# 328_ch340g.net
KiCad netlist of a schematic drawn in EAGLE
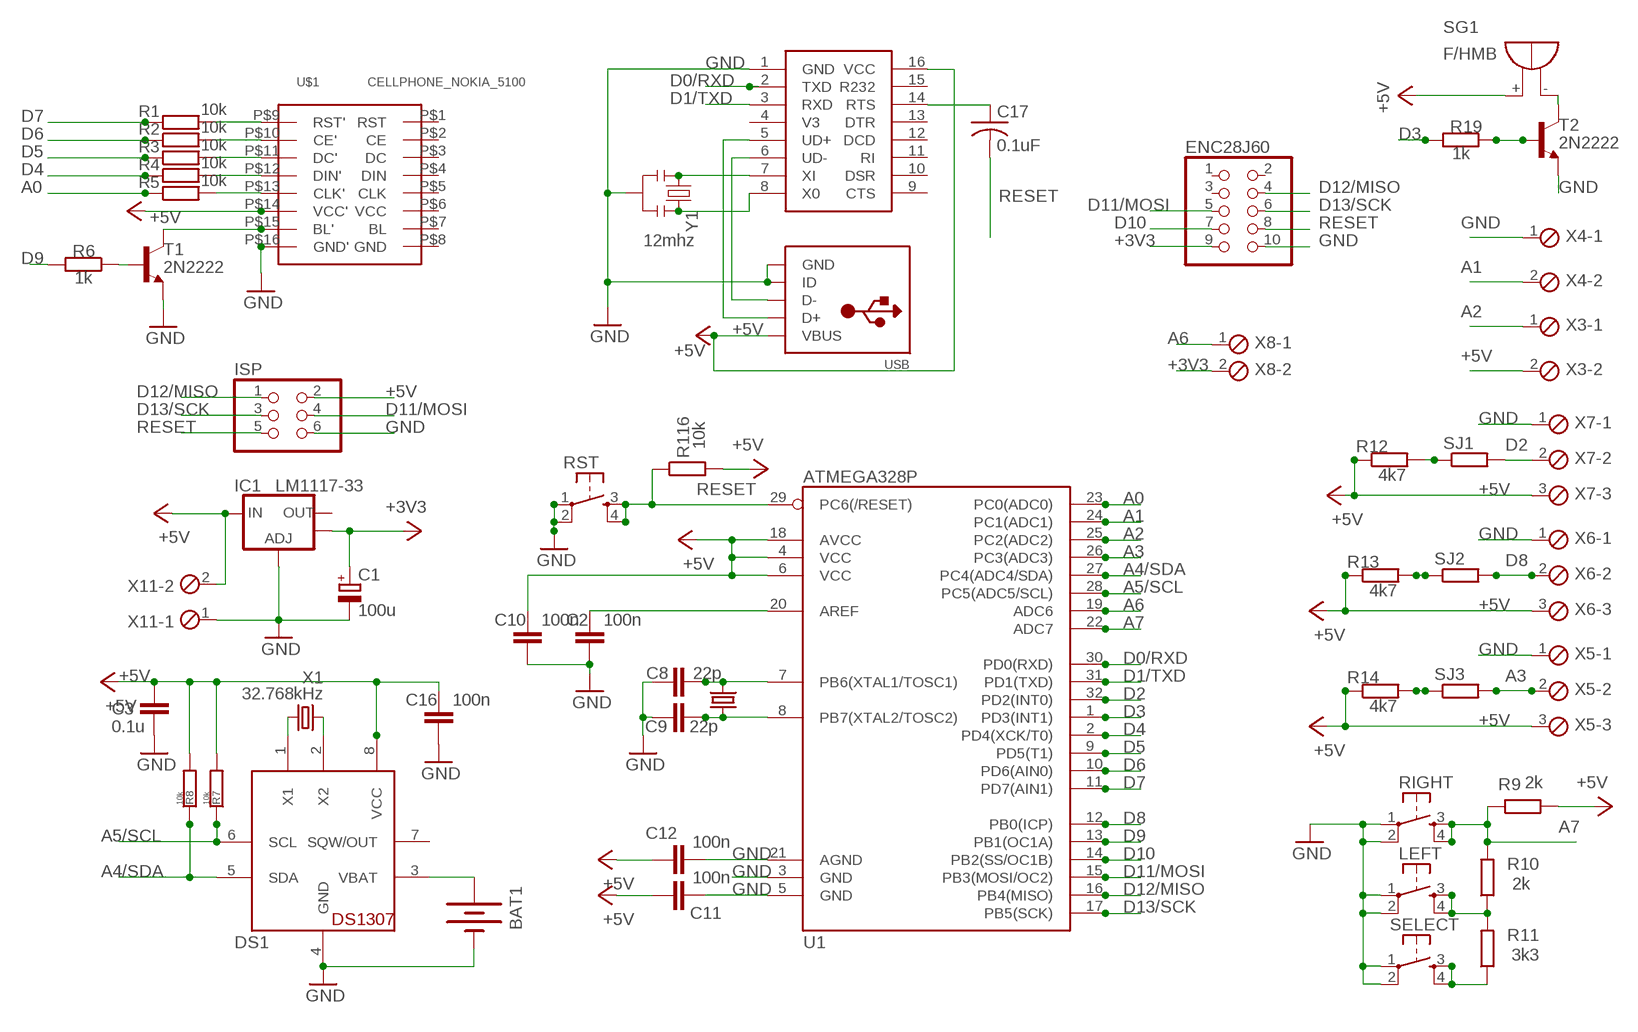
[diagram p0: schematic, sheet 1]

(export (version "E")
  (design (tool "Eeschema 10.0.6"))
  (components
    (comp (ref "BAT1")
      (value "BATTERY20PTH")
      (footprint "eagle-import:BATTCOM_20MM_PTH")
      (libsource (lib "eagle-import") (part "BATTERY20PTH"))
    )
    (comp (ref "C1")
      (value "100u")
      (footprint "eagle-import:E2-5")
      (libsource (lib "eagle-import") (part "CPOL-EUE2-5"))
    )
    (comp (ref "C2")
      (value "100n")
      (footprint "eagle-import:C0805")
      (libsource (lib "eagle-import") (part "resistor_C-EUC0805"))
    )
    (comp (ref "C3")
      (value "0.1u")
      (footprint "eagle-import:C0805")
      (libsource (lib "eagle-import") (part "C-EUC0805"))
    )
    (comp (ref "C8")
      (value "22p")
      (footprint "eagle-import:C0805")
      (libsource (lib "eagle-import") (part "resistor_C-EUC0805"))
    )
    (comp (ref "C9")
      (value "22p")
      (footprint "eagle-import:C0805")
      (libsource (lib "eagle-import") (part "resistor_C-EUC0805"))
    )
    (comp (ref "C10")
      (value "100n")
      (footprint "eagle-import:C0805")
      (libsource (lib "eagle-import") (part "resistor_C-EUC0805"))
    )
    (comp (ref "C11")
      (value "100n")
      (footprint "eagle-import:C0805")
      (libsource (lib "eagle-import") (part "resistor_C-EUC0805"))
    )
    (comp (ref "C12")
      (value "100n")
      (footprint "eagle-import:C0805")
      (libsource (lib "eagle-import") (part "resistor_C-EUC0805"))
    )
    (comp (ref "C16")
      (value "100n")
      (footprint "eagle-import:C0805")
      (libsource (lib "eagle-import") (part "resistor_C-EUC0805"))
    )
    (comp (ref "C17")
      (value "0.1uF")
      (footprint "eagle-import:C0805K")
      (libsource (lib "eagle-import") (part "C-USC0805K"))
    )
    (comp (ref "DS1")
      (value "DS1307")
      (footprint "eagle-import:SO08")
      (libsource (lib "eagle-import") (part "DS1307SOIC"))
    )
    (comp (ref "ENC28J60")
      (value "PINHD-2X5")
      (footprint "eagle-import:2X05")
      (libsource (lib "eagle-import") (part "PINHD-2X5"))
    )
    (comp (ref "IC1")
      (value "LM1117-33")
      (footprint "eagle-import:SOT223")
      (libsource (lib "eagle-import") (part "V_REG_LM1117SOT223"))
    )
    (comp (ref "ISP")
      (value "PINHD-2X3")
      (footprint "eagle-import:2X03")
      (libsource (lib "eagle-import") (part "PINHD-2X3"))
    )
    (comp (ref "LEFT")
      (value "TAC_SWITCHPTH")
      (footprint "eagle-import:TACTILE-PTH")
      (libsource (lib "eagle-import") (part "TAC_SWITCHPTH"))
    )
    (comp (ref "R1")
      (value "10k")
      (footprint "eagle-import:R0805")
      (libsource (lib "eagle-import") (part "R-EU_R0805"))
    )
    (comp (ref "R2")
      (value "10k")
      (footprint "eagle-import:R0805")
      (libsource (lib "eagle-import") (part "R-EU_R0805"))
    )
    (comp (ref "R3")
      (value "10k")
      (footprint "eagle-import:R0805")
      (libsource (lib "eagle-import") (part "R-EU_R0805"))
    )
    (comp (ref "R4")
      (value "10k")
      (footprint "eagle-import:R0805")
      (libsource (lib "eagle-import") (part "R-EU_R0805"))
    )
    (comp (ref "R5")
      (value "10k")
      (footprint "eagle-import:R0805")
      (libsource (lib "eagle-import") (part "R-EU_R0805"))
    )
    (comp (ref "R6")
      (value "1k")
      (footprint "eagle-import:R0805")
      (libsource (lib "eagle-import") (part "R-EU_R0805"))
    )
    (comp (ref "R7")
      (value "10k")
      (footprint "eagle-import:R0805")
      (libsource (lib "eagle-import") (part "R-EU_R0805"))
    )
    (comp (ref "R8")
      (value "10k")
      (footprint "eagle-import:R0805")
      (libsource (lib "eagle-import") (part "R-EU_R0805"))
    )
    (comp (ref "R9")
      (value "2k")
      (footprint "eagle-import:R0805")
      (libsource (lib "eagle-import") (part "R-EU_R0805"))
    )
    (comp (ref "R10")
      (value "2k")
      (footprint "eagle-import:R0805")
      (libsource (lib "eagle-import") (part "R-EU_R0805"))
    )
    (comp (ref "R11")
      (value "3k3")
      (footprint "eagle-import:R0805")
      (libsource (lib "eagle-import") (part "R-EU_R0805"))
    )
    (comp (ref "R12")
      (value "4k7")
      (footprint "eagle-import:R0805")
      (libsource (lib "eagle-import") (part "R-EU_R0805"))
    )
    (comp (ref "R13")
      (value "4k7")
      (footprint "eagle-import:R0805")
      (libsource (lib "eagle-import") (part "R-EU_R0805"))
    )
    (comp (ref "R14")
      (value "4k7")
      (footprint "eagle-import:R0805")
      (libsource (lib "eagle-import") (part "R-EU_R0805"))
    )
    (comp (ref "R19")
      (value "1k")
      (footprint "eagle-import:R0805")
      (libsource (lib "eagle-import") (part "R-EU_R0805"))
    )
    (comp (ref "R116")
      (value "10k")
      (footprint "eagle-import:R0805")
      (libsource (lib "eagle-import") (part "R-EU_R0805"))
    )
    (comp (ref "RIGHT")
      (value "TAC_SWITCHPTH")
      (footprint "eagle-import:TACTILE-PTH")
      (libsource (lib "eagle-import") (part "TAC_SWITCHPTH"))
    )
    (comp (ref "RST")
      (value "TAC_SWITCHPTH")
      (footprint "eagle-import:TACTILE-PTH")
      (libsource (lib "eagle-import") (part "TAC_SWITCHPTH"))
    )
    (comp (ref "SELECT")
      (value "TAC_SWITCHPTH")
      (footprint "eagle-import:TACTILE-PTH")
      (libsource (lib "eagle-import") (part "TAC_SWITCHPTH"))
    )
    (comp (ref "SG1")
      (value "F/HMB")
      (footprint "eagle-import:F_HMB")
      (libsource (lib "eagle-import") (part "F/HMB"))
    )
    (comp (ref "SJ1")
      (value "R-EU_R0402")
      (footprint "eagle-import:R0402")
      (libsource (lib "eagle-import") (part "R-EU_R0402"))
    )
    (comp (ref "SJ2")
      (value "R-EU_R0402")
      (footprint "eagle-import:R0402")
      (libsource (lib "eagle-import") (part "R-EU_R0402"))
    )
    (comp (ref "SJ3")
      (value "R-EU_R0402")
      (footprint "eagle-import:R0402")
      (libsource (lib "eagle-import") (part "R-EU_R0402"))
    )
    (comp (ref "T1")
      (value "2N2222")
      (footprint "eagle-import:TO92-EBC-OVAL")
      (libsource (lib "eagle-import") (part "2N2222"))
    )
    (comp (ref "T2")
      (value "2N2222")
      (footprint "eagle-import:TO92-EBC-OVAL")
      (libsource (lib "eagle-import") (part "2N2222"))
    )
    (comp (ref "U$1")
      (value "CELLPHONE_NOKIA_5100")
      (footprint "eagle-import:CELLPHONE_NOKIA_5100_SPARKFUN")
      (libsource (lib "eagle-import") (part "CELLPHONE_NOKIA_5100"))
    )
    (comp (ref "U$2")
      (value "CH340G")
      (footprint "eagle-import:SO016")
      (libsource (lib "eagle-import") (part "CH340G"))
    )
    (comp (ref "U1")
      (value "ATMEGA328P")
      (footprint "eagle-import:TQFP32-08")
      (libsource (lib "eagle-import") (part "ATMEGA328_SMT"))
    )
    (comp (ref "USB")
      (value "USBMOLEX")
      (footprint "eagle-import:USB-MINIB-THM-MOLEX")
      (libsource (lib "eagle-import") (part "USBMOLEX"))
    )
    (comp (ref "X1")
      (value "32.768kHz")
      (footprint "eagle-import:TC26H")
      (libsource (lib "eagle-import") (part "crystal_CRYSTALTC26H"))
    )
    (comp (ref "X2")
      (value "16MHz")
      (footprint "eagle-import:HC49US")
      (libsource (lib "eagle-import") (part "CRYSTALHC49US"))
    )
    (comp (ref "X3")
      (value "MPT2")
      (footprint "eagle-import:2POL254")
      (libsource (lib "eagle-import") (part "MPT2"))
    )
    (comp (ref "X4")
      (value "MPT2")
      (footprint "eagle-import:2POL254")
      (libsource (lib "eagle-import") (part "MPT2"))
    )
    (comp (ref "X5")
      (value "MPT3")
      (footprint "eagle-import:3POL254")
      (libsource (lib "eagle-import") (part "MPT3"))
    )
    (comp (ref "X6")
      (value "MPT3")
      (footprint "eagle-import:3POL254")
      (libsource (lib "eagle-import") (part "MPT3"))
    )
    (comp (ref "X7")
      (value "MPT3")
      (footprint "eagle-import:3POL254")
      (libsource (lib "eagle-import") (part "MPT3"))
    )
    (comp (ref "X8")
      (value "MPT2")
      (footprint "eagle-import:2POL254")
      (libsource (lib "eagle-import") (part "MPT2"))
    )
    (comp (ref "X11")
      (value "MPT2")
      (footprint "eagle-import:2POL254")
      (fields (field (name "OC_FARNELL") "unknown") (field (name "OC_NEWARK") "unknown"))
      (libsource (lib "eagle-import") (part "MPT2"))
    )
    (comp (ref "Y1")
      (value "12mhz")
      (footprint "eagle-import:RESONATOR-PTH")
      (libsource (lib "eagle-import") (part "RESONATORPTH"))
    )
  )
  (nets
    (net (code "1") (name "+3V3") (class "Default")
      (node (ref "C1") (pin "+") (pinfunction "+_+") (pintype "passive"))
      (node (ref "ENC28J60") (pin "9") (pinfunction "9_9") (pintype "passive"))
      (node (ref "IC1") (pin "4") (pinfunction "OUT_4") (pintype "bidirectional"))
      (node (ref "X8") (pin "2") (pinfunction "1_2") (pintype "passive"))
    )
    (net (code "2") (name "+5V") (class "Default")
      (node (ref "C10") (pin "1") (pinfunction "1_1") (pintype "passive"))
      (node (ref "C11") (pin "2") (pinfunction "2_2") (pintype "passive"))
      (node (ref "C12") (pin "2") (pinfunction "2_2") (pintype "passive"))
      (node (ref "C16") (pin "1") (pinfunction "1_1") (pintype "passive"))
      (node (ref "C3") (pin "1") (pinfunction "1_1") (pintype "passive"))
      (node (ref "DS1") (pin "8") (pinfunction "VCC_8") (pintype "power_in"))
      (node (ref "IC1") (pin "3") (pinfunction "IN_3") (pintype "input"))
      (node (ref "ISP") (pin "2") (pinfunction "2_2") (pintype "passive"))
      (node (ref "R116") (pin "2") (pinfunction "2_2") (pintype "passive"))
      (node (ref "R12") (pin "1") (pinfunction "1_1") (pintype "passive"))
      (node (ref "R13") (pin "1") (pinfunction "1_1") (pintype "passive"))
      (node (ref "R14") (pin "1") (pinfunction "1_1") (pintype "passive"))
      (node (ref "R7") (pin "2") (pinfunction "2_2") (pintype "passive"))
      (node (ref "R8") (pin "2") (pinfunction "2_2") (pintype "passive"))
      (node (ref "R9") (pin "2") (pinfunction "2_2") (pintype "passive"))
      (node (ref "SG1") (pin "+") (pinfunction "+_+") (pintype "passive"))
      (node (ref "U$1") (pin "P$14") (pinfunction "VCC'_P$14") (pintype "bidirectional"))
      (node (ref "U$2") (pin "16") (pinfunction "VCC_16") (pintype "bidirectional"))
      (node (ref "U1") (pin "18") (pinfunction "AVCC_18") (pintype "bidirectional"))
      (node (ref "U1") (pin "4") (pinfunction "VCC_4") (pintype "bidirectional"))
      (node (ref "U1") (pin "6") (pinfunction "VCC_6") (pintype "bidirectional"))
      (node (ref "USB") (pin "VBUS") (pinfunction "VBUS_VBUS") (pintype "power_in"))
      (node (ref "X11") (pin "2") (pinfunction "1_2") (pintype "passive"))
      (node (ref "X3") (pin "2") (pinfunction "1_2") (pintype "passive"))
      (node (ref "X5") (pin "3") (pinfunction "1_3") (pintype "passive"))
      (node (ref "X6") (pin "3") (pinfunction "1_3") (pintype "passive"))
      (node (ref "X7") (pin "3") (pinfunction "1_3") (pintype "passive"))
    )
    (net (code "3") (name "/A0") (class "Default")
      (node (ref "R5") (pin "1") (pinfunction "1_1") (pintype "passive"))
      (node (ref "U1") (pin "23") (pinfunction "PC0(ADC0)_23") (pintype "bidirectional"))
    )
    (net (code "4") (name "/A1") (class "Default")
      (node (ref "U1") (pin "24") (pinfunction "PC1(ADC1)_24") (pintype "bidirectional"))
      (node (ref "X4") (pin "2") (pinfunction "1_2") (pintype "passive"))
    )
    (net (code "5") (name "/A2") (class "Default")
      (node (ref "U1") (pin "25") (pinfunction "PC2(ADC2)_25") (pintype "bidirectional"))
      (node (ref "X3") (pin "1") (pinfunction "1_1") (pintype "passive"))
    )
    (net (code "6") (name "/A3") (class "Default")
      (node (ref "SJ3") (pin "2") (pinfunction "2_2") (pintype "passive"))
      (node (ref "U1") (pin "26") (pinfunction "PC3(ADC3)_26") (pintype "bidirectional"))
      (node (ref "X5") (pin "2") (pinfunction "1_2") (pintype "passive"))
    )
    (net (code "7") (name "/A4{slash}SDA") (class "Default")
      (node (ref "DS1") (pin "5") (pinfunction "SDA_5") (pintype "bidirectional"))
      (node (ref "R8") (pin "1") (pinfunction "1_1") (pintype "passive"))
      (node (ref "U1") (pin "27") (pinfunction "PC4(ADC4/SDA)_27") (pintype "bidirectional"))
    )
    (net (code "8") (name "/A5{slash}SCL") (class "Default")
      (node (ref "DS1") (pin "6") (pinfunction "SCL_6") (pintype "bidirectional"))
      (node (ref "R7") (pin "1") (pinfunction "1_1") (pintype "passive"))
      (node (ref "U1") (pin "28") (pinfunction "PC5(ADC5/SCL)_28") (pintype "bidirectional"))
    )
    (net (code "9") (name "/A6") (class "Default")
      (node (ref "U1") (pin "19") (pinfunction "ADC6_19") (pintype "bidirectional"))
      (node (ref "X8") (pin "1") (pinfunction "1_1") (pintype "passive"))
    )
    (net (code "10") (name "/A7") (class "Default")
      (node (ref "R10") (pin "2") (pinfunction "2_2") (pintype "passive"))
      (node (ref "R9") (pin "1") (pinfunction "1_1") (pintype "passive"))
      (node (ref "RIGHT") (pin "3") (pinfunction "3_3") (pintype "passive"))
      (node (ref "RIGHT") (pin "4") (pinfunction "4_4") (pintype "passive"))
      (node (ref "U1") (pin "22") (pinfunction "ADC7_22") (pintype "bidirectional"))
    )
    (net (code "11") (name "/D0{slash}RXD") (class "Default")
      (node (ref "U$2") (pin "2") (pinfunction "TXD_2") (pintype "bidirectional"))
      (node (ref "U1") (pin "30") (pinfunction "PD0(RXD)_30") (pintype "bidirectional"))
    )
    (net (code "12") (name "/D1{slash}TXD") (class "Default")
      (node (ref "U$2") (pin "3") (pinfunction "RXD_3") (pintype "bidirectional"))
      (node (ref "U1") (pin "31") (pinfunction "PD1(TXD)_31") (pintype "bidirectional"))
    )
    (net (code "13") (name "/D2") (class "Default")
      (node (ref "SJ1") (pin "2") (pinfunction "2_2") (pintype "passive"))
      (node (ref "U1") (pin "32") (pinfunction "PD2(INT0)_32") (pintype "bidirectional"))
      (node (ref "X7") (pin "2") (pinfunction "1_2") (pintype "passive"))
    )
    (net (code "14") (name "/D3") (class "Default")
      (node (ref "R19") (pin "2") (pinfunction "2_2") (pintype "passive"))
      (node (ref "U1") (pin "1") (pinfunction "PD3(INT1)_1") (pintype "bidirectional"))
    )
    (net (code "15") (name "/D4") (class "Default")
      (node (ref "R4") (pin "1") (pinfunction "1_1") (pintype "passive"))
      (node (ref "U1") (pin "2") (pinfunction "PD4(XCK/T0)_2") (pintype "bidirectional"))
    )
    (net (code "16") (name "/D5") (class "Default")
      (node (ref "R3") (pin "1") (pinfunction "1_1") (pintype "passive"))
      (node (ref "U1") (pin "9") (pinfunction "PD5(T1)_9") (pintype "bidirectional"))
    )
    (net (code "17") (name "/D6") (class "Default")
      (node (ref "R2") (pin "1") (pinfunction "1_1") (pintype "passive"))
      (node (ref "U1") (pin "10") (pinfunction "PD6(AIN0)_10") (pintype "bidirectional"))
    )
    (net (code "18") (name "/D7") (class "Default")
      (node (ref "R1") (pin "1") (pinfunction "1_1") (pintype "passive"))
      (node (ref "U1") (pin "11") (pinfunction "PD7(AIN1)_11") (pintype "bidirectional"))
    )
    (net (code "19") (name "/D8") (class "Default")
      (node (ref "SJ2") (pin "2") (pinfunction "2_2") (pintype "passive"))
      (node (ref "U1") (pin "12") (pinfunction "PB0(ICP)_12") (pintype "bidirectional"))
      (node (ref "X6") (pin "2") (pinfunction "1_2") (pintype "passive"))
    )
    (net (code "20") (name "/D9") (class "Default")
      (node (ref "R6") (pin "2") (pinfunction "2_2") (pintype "passive"))
      (node (ref "U1") (pin "13") (pinfunction "PB1(OC1A)_13") (pintype "bidirectional"))
    )
    (net (code "21") (name "/D10") (class "Default")
      (node (ref "ENC28J60") (pin "7") (pinfunction "7_7") (pintype "passive"))
      (node (ref "U1") (pin "14") (pinfunction "PB2(SS/OC1B)_14") (pintype "bidirectional"))
    )
    (net (code "22") (name "/D11{slash}MOSI") (class "Default")
      (node (ref "ENC28J60") (pin "5") (pinfunction "5_5") (pintype "passive"))
      (node (ref "ISP") (pin "4") (pinfunction "4_4") (pintype "passive"))
      (node (ref "U1") (pin "15") (pinfunction "PB3(MOSI/OC2)_15") (pintype "bidirectional"))
    )
    (net (code "23") (name "/D12{slash}MISO") (class "Default")
      (node (ref "ENC28J60") (pin "4") (pinfunction "4_4") (pintype "passive"))
      (node (ref "ISP") (pin "1") (pinfunction "1_1") (pintype "passive"))
      (node (ref "U1") (pin "16") (pinfunction "PB4(MISO)_16") (pintype "bidirectional"))
    )
    (net (code "24") (name "/D13{slash}SCK") (class "Default")
      (node (ref "ENC28J60") (pin "6") (pinfunction "6_6") (pintype "passive"))
      (node (ref "ISP") (pin "3") (pinfunction "3_3") (pintype "passive"))
      (node (ref "U1") (pin "17") (pinfunction "PB5(SCK)_17") (pintype "bidirectional"))
    )
    (net (code "25") (name "/RESET") (class "Default")
      (node (ref "C17") (pin "2") (pinfunction "2_2") (pintype "passive"))
      (node (ref "ENC28J60") (pin "8") (pinfunction "8_8") (pintype "passive"))
      (node (ref "ISP") (pin "5") (pinfunction "5_5") (pintype "passive"))
      (node (ref "R116") (pin "1") (pinfunction "1_1") (pintype "passive"))
      (node (ref "RST") (pin "3") (pinfunction "3_3") (pintype "passive"))
      (node (ref "RST") (pin "4") (pinfunction "4_4") (pintype "passive"))
      (node (ref "U1") (pin "29") (pinfunction "PC6(/RESET)_29") (pintype "bidirectional"))
    )
    (net (code "26") (name "GND") (class "Default")
      (node (ref "BAT1") (pin "2") (pinfunction "-_2") (pintype "power_in"))
      (node (ref "C1") (pin "-") (pinfunction "-_-") (pintype "passive"))
      (node (ref "C10") (pin "2") (pinfunction "2_2") (pintype "passive"))
      (node (ref "C11") (pin "1") (pinfunction "1_1") (pintype "passive"))
      (node (ref "C12") (pin "1") (pinfunction "1_1") (pintype "passive"))
      (node (ref "C16") (pin "2") (pinfunction "2_2") (pintype "passive"))
      (node (ref "C2") (pin "2") (pinfunction "2_2") (pintype "passive"))
      (node (ref "C3") (pin "2") (pinfunction "2_2") (pintype "passive"))
      (node (ref "C8") (pin "1") (pinfunction "1_1") (pintype "passive"))
      (node (ref "C9") (pin "1") (pinfunction "1_1") (pintype "passive"))
      (node (ref "DS1") (pin "4") (pinfunction "GND_4") (pintype "power_in"))
      (node (ref "ENC28J60") (pin "10") (pinfunction "10_10") (pintype "passive"))
      (node (ref "IC1") (pin "1") (pinfunction "ADJ_1") (pintype "input"))
      (node (ref "ISP") (pin "6") (pinfunction "6_6") (pintype "passive"))
      (node (ref "LEFT") (pin "1") (pinfunction "1_1") (pintype "passive"))
      (node (ref "LEFT") (pin "2") (pinfunction "2_2") (pintype "passive"))
      (node (ref "RIGHT") (pin "1") (pinfunction "1_1") (pintype "passive"))
      (node (ref "RIGHT") (pin "2") (pinfunction "2_2") (pintype "passive"))
      (node (ref "RST") (pin "1") (pinfunction "1_1") (pintype "passive"))
      (node (ref "RST") (pin "2") (pinfunction "2_2") (pintype "passive"))
      (node (ref "SELECT") (pin "1") (pinfunction "1_1") (pintype "passive"))
      (node (ref "SELECT") (pin "2") (pinfunction "2_2") (pintype "passive"))
      (node (ref "T1") (pin "E") (pinfunction "E_E") (pintype "passive"))
      (node (ref "T2") (pin "E") (pinfunction "E_E") (pintype "passive"))
      (node (ref "U$1") (pin "P$16") (pinfunction "GND'_P$16") (pintype "bidirectional"))
      (node (ref "U$2") (pin "1") (pinfunction "GND_1") (pintype "bidirectional"))
      (node (ref "U1") (pin "21") (pinfunction "AGND_21") (pintype "bidirectional"))
      (node (ref "U1") (pin "3") (pinfunction "GND_3") (pintype "bidirectional"))
      (node (ref "U1") (pin "5") (pinfunction "GND_5") (pintype "bidirectional"))
      (node (ref "USB") (pin "GND") (pinfunction "GND_GND") (pintype "power_in"))
      (node (ref "USB") (pin "ID") (pinfunction "ID_ID") (pintype "bidirectional"))
      (node (ref "X11") (pin "1") (pinfunction "1_1") (pintype "passive"))
      (node (ref "X4") (pin "1") (pinfunction "1_1") (pintype "passive"))
      (node (ref "X5") (pin "1") (pinfunction "1_1") (pintype "passive"))
      (node (ref "X6") (pin "1") (pinfunction "1_1") (pintype "passive"))
      (node (ref "X7") (pin "1") (pinfunction "1_1") (pintype "passive"))
      (node (ref "Y1") (pin "2") (pinfunction "2_2") (pintype "passive"))
    )
    (net (code "27") (name "Net-(BAT1-+)") (class "Default")
      (node (ref "BAT1") (pin "1") (pinfunction "+_1") (pintype "power_in"))
      (node (ref "DS1") (pin "3") (pinfunction "VBAT_3") (pintype "power_in"))
    )
    (net (code "28") (name "Net-(DS1-X1)") (class "Default")
      (node (ref "DS1") (pin "1") (pinfunction "X1_1") (pintype "passive"))
      (node (ref "X1") (pin "2") (pinfunction "2_2") (pintype "passive"))
    )
    (net (code "29") (name "Net-(DS1-X2)") (class "Default")
      (node (ref "DS1") (pin "2") (pinfunction "X2_2") (pintype "passive"))
      (node (ref "X1") (pin "1") (pinfunction "1_1") (pintype "passive"))
    )
    (net (code "30") (name "Net-(LEFT-Pad3)") (class "Default")
      (node (ref "LEFT") (pin "3") (pinfunction "3_3") (pintype "passive"))
      (node (ref "LEFT") (pin "4") (pinfunction "4_4") (pintype "passive"))
      (node (ref "R10") (pin "1") (pinfunction "1_1") (pintype "passive"))
      (node (ref "R11") (pin "2") (pinfunction "2_2") (pintype "passive"))
    )
    (net (code "31") (name "Net-(R6-Pad1)") (class "Default")
      (node (ref "R6") (pin "1") (pinfunction "1_1") (pintype "passive"))
      (node (ref "T1") (pin "B") (pinfunction "B_B") (pintype "passive"))
    )
    (net (code "32") (name "Net-(R11-Pad1)") (class "Default")
      (node (ref "R11") (pin "1") (pinfunction "1_1") (pintype "passive"))
      (node (ref "SELECT") (pin "3") (pinfunction "3_3") (pintype "passive"))
      (node (ref "SELECT") (pin "4") (pinfunction "4_4") (pintype "passive"))
    )
    (net (code "33") (name "Net-(R12-Pad2)") (class "Default")
      (node (ref "R12") (pin "2") (pinfunction "2_2") (pintype "passive"))
      (node (ref "SJ1") (pin "1") (pinfunction "1_1") (pintype "passive"))
    )
    (net (code "34") (name "Net-(R13-Pad2)") (class "Default")
      (node (ref "R13") (pin "2") (pinfunction "2_2") (pintype "passive"))
      (node (ref "SJ2") (pin "1") (pinfunction "1_1") (pintype "passive"))
    )
    (net (code "35") (name "Net-(R14-Pad2)") (class "Default")
      (node (ref "R14") (pin "2") (pinfunction "2_2") (pintype "passive"))
      (node (ref "SJ3") (pin "1") (pinfunction "1_1") (pintype "passive"))
    )
    (net (code "36") (name "Net-(R19-Pad1)") (class "Default")
      (node (ref "R19") (pin "1") (pinfunction "1_1") (pintype "passive"))
      (node (ref "T2") (pin "B") (pinfunction "B_B") (pintype "passive"))
    )
    (net (code "37") (name "Net-(SG1-Pad-)") (class "Default")
      (node (ref "SG1") (pin "-") (pinfunction "-_-") (pintype "passive"))
      (node (ref "T2") (pin "C") (pinfunction "C_C") (pintype "passive"))
    )
    (net (code "38") (name "Net-(U$1-BL')") (class "Default")
      (node (ref "T1") (pin "C") (pinfunction "C_C") (pintype "passive"))
      (node (ref "U$1") (pin "P$15") (pinfunction "BL'_P$15") (pintype "bidirectional"))
    )
    (net (code "39") (name "Net-(U$1-CE')") (class "Default")
      (node (ref "R2") (pin "2") (pinfunction "2_2") (pintype "passive"))
      (node (ref "U$1") (pin "P$10") (pinfunction "CE'_P$10") (pintype "bidirectional"))
    )
    (net (code "40") (name "Net-(U$1-CLK')") (class "Default")
      (node (ref "R5") (pin "2") (pinfunction "2_2") (pintype "passive"))
      (node (ref "U$1") (pin "P$13") (pinfunction "CLK'_P$13") (pintype "bidirectional"))
    )
    (net (code "41") (name "Net-(U$1-DC')") (class "Default")
      (node (ref "R3") (pin "2") (pinfunction "2_2") (pintype "passive"))
      (node (ref "U$1") (pin "P$11") (pinfunction "DC'_P$11") (pintype "bidirectional"))
    )
    (net (code "42") (name "Net-(U$1-DIN')") (class "Default")
      (node (ref "R4") (pin "2") (pinfunction "2_2") (pintype "passive"))
      (node (ref "U$1") (pin "P$12") (pinfunction "DIN'_P$12") (pintype "bidirectional"))
    )
    (net (code "43") (name "Net-(U$1-RST')") (class "Default")
      (node (ref "R1") (pin "2") (pinfunction "2_2") (pintype "passive"))
      (node (ref "U$1") (pin "P$9") (pinfunction "RST'_P$9") (pintype "bidirectional"))
    )
    (net (code "44") (name "Net-(U$2-RTS)") (class "Default")
      (node (ref "C17") (pin "1") (pinfunction "1_1") (pintype "passive"))
      (node (ref "U$2") (pin "14") (pinfunction "RTS_14") (pintype "bidirectional"))
    )
    (net (code "45") (name "Net-(U$2-UD+)") (class "Default")
      (node (ref "U$2") (pin "5") (pinfunction "UD+_5") (pintype "bidirectional"))
      (node (ref "USB") (pin "D+") (pinfunction "D+_D+") (pintype "bidirectional"))
    )
    (net (code "46") (name "Net-(U$2-UD-)") (class "Default")
      (node (ref "U$2") (pin "6") (pinfunction "UD-_6") (pintype "bidirectional"))
      (node (ref "USB") (pin "D-") (pinfunction "D-_D-") (pintype "bidirectional"))
    )
    (net (code "47") (name "Net-(U$2-X0)") (class "Default")
      (node (ref "U$2") (pin "8") (pinfunction "X0_8") (pintype "bidirectional"))
      (node (ref "Y1") (pin "3") (pinfunction "3_3") (pintype "passive"))
    )
    (net (code "48") (name "Net-(U$2-XI)") (class "Default")
      (node (ref "U$2") (pin "7") (pinfunction "XI_7") (pintype "bidirectional"))
      (node (ref "Y1") (pin "1") (pinfunction "1_1") (pintype "passive"))
    )
    (net (code "49") (name "Net-(U1-AREF)") (class "Default")
      (node (ref "C2") (pin "1") (pinfunction "1_1") (pintype "passive"))
      (node (ref "U1") (pin "20") (pinfunction "AREF_20") (pintype "bidirectional"))
    )
    (net (code "50") (name "Net-(U1-PB6(XTAL1{slash}TOSC1))") (class "Default")
      (node (ref "C8") (pin "2") (pinfunction "2_2") (pintype "passive"))
      (node (ref "U1") (pin "7") (pinfunction "PB6(XTAL1/TOSC1)_7") (pintype "bidirectional"))
      (node (ref "X2") (pin "2") (pinfunction "2_2") (pintype "passive"))
    )
    (net (code "51") (name "Net-(U1-PB7(XTAL2{slash}TOSC2))") (class "Default")
      (node (ref "C9") (pin "2") (pinfunction "2_2") (pintype "passive"))
      (node (ref "U1") (pin "8") (pinfunction "PB7(XTAL2/TOSC2)_8") (pintype "bidirectional"))
      (node (ref "X2") (pin "1") (pinfunction "1_1") (pintype "passive"))
    )
    (net (code "52") (name "unconnected-(DS1-SQW{slash}OUT-Pad7)") (class "Default")
      (node (ref "DS1") (pin "7") (pinfunction "SQW/OUT_7") (pintype "bidirectional"))
    )
    (net (code "53") (name "unconnected-(ENC28J60-Pad1)") (class "Default")
      (node (ref "ENC28J60") (pin "1") (pinfunction "1_1") (pintype "passive"))
    )
    (net (code "54") (name "unconnected-(ENC28J60-Pad2)") (class "Default")
      (node (ref "ENC28J60") (pin "2") (pinfunction "2_2") (pintype "passive"))
    )
    (net (code "55") (name "unconnected-(ENC28J60-Pad3)") (class "Default")
      (node (ref "ENC28J60") (pin "3") (pinfunction "3_3") (pintype "passive"))
    )
    (net (code "56") (name "unconnected-(IC1-OUT-Pad2)") (class "Default")
      (node (ref "IC1") (pin "2") (pinfunction "OUT_2") (pintype "bidirectional"))
    )
    (net (code "57") (name "unconnected-(U$1-BL-PadP$7)") (class "Default")
      (node (ref "U$1") (pin "P$7") (pinfunction "BL_P$7") (pintype "bidirectional"))
    )
    (net (code "58") (name "unconnected-(U$1-CE-PadP$2)") (class "Default")
      (node (ref "U$1") (pin "P$2") (pinfunction "CE_P$2") (pintype "bidirectional"))
    )
    (net (code "59") (name "unconnected-(U$1-CLK-PadP$5)") (class "Default")
      (node (ref "U$1") (pin "P$5") (pinfunction "CLK_P$5") (pintype "bidirectional"))
    )
    (net (code "60") (name "unconnected-(U$1-DC-PadP$3)") (class "Default")
      (node (ref "U$1") (pin "P$3") (pinfunction "DC_P$3") (pintype "bidirectional"))
    )
    (net (code "61") (name "unconnected-(U$1-DIN-PadP$4)") (class "Default")
      (node (ref "U$1") (pin "P$4") (pinfunction "DIN_P$4") (pintype "bidirectional"))
    )
    (net (code "62") (name "unconnected-(U$1-GND-PadP$8)") (class "Default")
      (node (ref "U$1") (pin "P$8") (pinfunction "GND_P$8") (pintype "bidirectional"))
    )
    (net (code "63") (name "unconnected-(U$1-RST-PadP$1)") (class "Default")
      (node (ref "U$1") (pin "P$1") (pinfunction "RST_P$1") (pintype "bidirectional"))
    )
    (net (code "64") (name "unconnected-(U$1-VCC-PadP$6)") (class "Default")
      (node (ref "U$1") (pin "P$6") (pinfunction "VCC_P$6") (pintype "bidirectional"))
    )
    (net (code "65") (name "unconnected-(U$2-CTS-Pad9)") (class "Default")
      (node (ref "U$2") (pin "9") (pinfunction "CTS_9") (pintype "bidirectional"))
    )
    (net (code "66") (name "unconnected-(U$2-DCD-Pad12)") (class "Default")
      (node (ref "U$2") (pin "12") (pinfunction "DCD_12") (pintype "bidirectional"))
    )
    (net (code "67") (name "unconnected-(U$2-DSR-Pad10)") (class "Default")
      (node (ref "U$2") (pin "10") (pinfunction "DSR_10") (pintype "bidirectional"))
    )
    (net (code "68") (name "unconnected-(U$2-DTR-Pad13)") (class "Default")
      (node (ref "U$2") (pin "13") (pinfunction "DTR_13") (pintype "bidirectional"))
    )
    (net (code "69") (name "unconnected-(U$2-R232-Pad15)") (class "Default")
      (node (ref "U$2") (pin "15") (pinfunction "R232_15") (pintype "bidirectional"))
    )
    (net (code "70") (name "unconnected-(U$2-RI-Pad11)") (class "Default")
      (node (ref "U$2") (pin "11") (pinfunction "RI_11") (pintype "bidirectional"))
    )
    (net (code "71") (name "unconnected-(U$2-V3-Pad4)") (class "Default")
      (node (ref "U$2") (pin "4") (pinfunction "V3_4") (pintype "bidirectional"))
    )
  )
)
